# MCU.net
KiCad netlist of a schematic drawn in Altium Designer
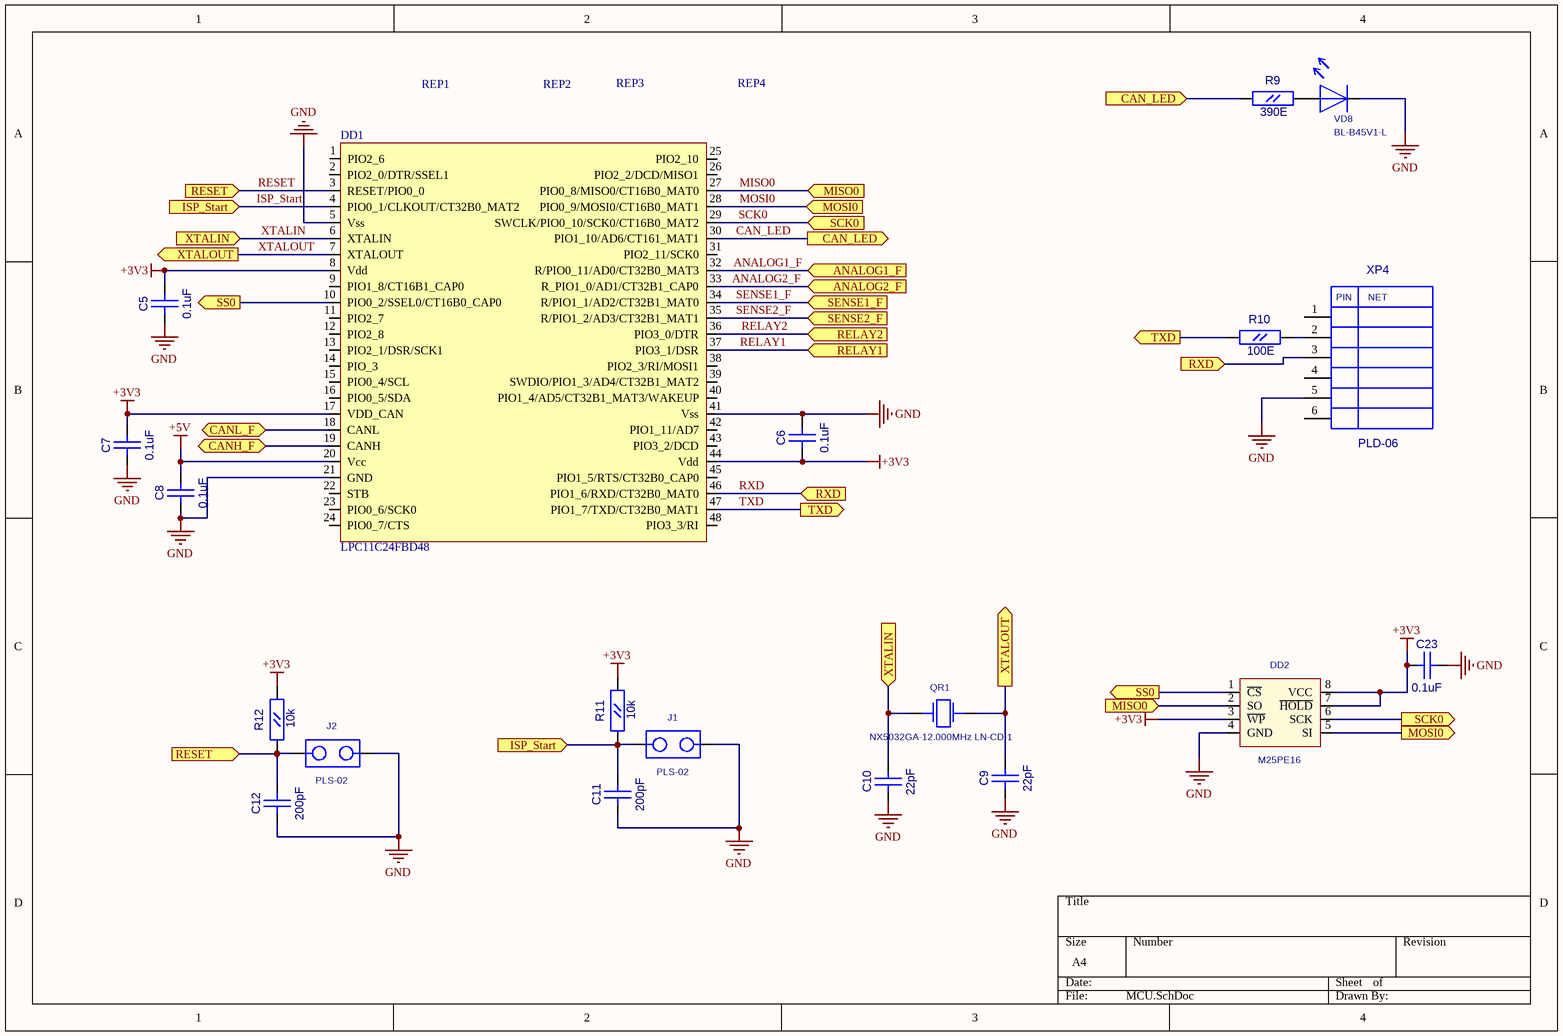
[diagram p0: MCU.SchDoc]

(export (version "E")
  (design (tool "Eeschema 10.0.6"))
  (components
    (comp (ref "C5")
      (value "0.1uF")
      (footprint "CC0603")
      (description "CC0603")
      (libsource (lib "gprs_modem_2") (part "CC0603"))
    )
    (comp (ref "C6")
      (value "0.1uF")
      (footprint "CC0603")
      (description "CC0603")
      (libsource (lib "gprs_modem_2") (part "CC0603"))
    )
    (comp (ref "C7")
      (value "0.1uF")
      (footprint "CC0603")
      (description "CC0603")
      (libsource (lib "gprs_modem_2") (part "CC0603"))
    )
    (comp (ref "C8")
      (value "0.1uF")
      (footprint "CC0603")
      (description "CC0603")
      (libsource (lib "gprs_modem_2") (part "CC0603"))
    )
    (comp (ref "C9")
      (value "22pF")
      (footprint "CC0603")
      (description "CC0603")
      (libsource (lib "gprs_modem_2") (part "CC0603"))
    )
    (comp (ref "C10")
      (value "22pF")
      (footprint "CC0603")
      (description "CC0603")
      (libsource (lib "gprs_modem_2") (part "CC0603"))
    )
    (comp (ref "C11")
      (value "200pF")
      (footprint "CC0603")
      (description "CC0603")
      (libsource (lib "gprs_modem_2") (part "CC0603"))
    )
    (comp (ref "C12")
      (value "200pF")
      (footprint "CC0603")
      (description "CC0603")
      (libsource (lib "gprs_modem_2") (part "CC0603"))
    )
    (comp (ref "C23")
      (value "0.1uF")
      (footprint "CC0603")
      (description "CC0603")
      (libsource (lib "gprs_modem_2") (part "CC0603"))
    )
    (comp (ref "DD1")
      (value "LPC11C24FBD48")
      (footprint "LQFP-48")
      (libsource (lib "gprs_modem_2") (part "LPC11C24FBD48"))
    )
    (comp (ref "DD2")
      (value "M25PE16")
      (footprint "EIAJ_SO8")
      (description "S25FL016A0LMFI01")
      (libsource (lib "gprs_modem_2") (part "S25FL016A0LMFI01"))
    )
    (comp (ref "J1") (value "PLS-02") (footprint "PLS-02") (libsource (lib "gprs_modem_2") (part "PLS-02")))
    (comp (ref "J2") (value "PLS-02") (footprint "PLS-02") (libsource (lib "gprs_modem_2") (part "PLS-02")))
    (comp (ref "QR1")
      (value "NX5032GA-12.000MHz LN-CD-1")
      (footprint "AC5032_2")
      (description "AC5032/2")
      (libsource (lib "gprs_modem_2") (part "AC5032_2"))
    )
    (comp (ref "R9")
      (value "390E")
      (footprint "RC0603")
      (description "RC0603")
      (libsource (lib "gprs_modem_2") (part "RC0603"))
    )
    (comp (ref "R10")
      (value "100E")
      (footprint "RC0603")
      (description "RC0603")
      (libsource (lib "gprs_modem_2") (part "RC0603"))
    )
    (comp (ref "R11")
      (value "10k")
      (footprint "RC0603")
      (description "RC0603")
      (libsource (lib "gprs_modem_2") (part "RC0603"))
    )
    (comp (ref "R12")
      (value "10k")
      (footprint "RC0603")
      (description "RC0603")
      (libsource (lib "gprs_modem_2") (part "RC0603"))
    )
    (comp (ref "REP1")
      (value "REPER_POINT_1.2")
      (footprint "REPER1.2")
      (description "REPER1.2")
      (libsource (lib "gprs_modem_2") (part "REPER1.2"))
    )
    (comp (ref "REP2")
      (value "REPER_POINT_1.2")
      (footprint "REPER1.2")
      (description "REPER1.2")
      (libsource (lib "gprs_modem_2") (part "REPER1.2"))
    )
    (comp (ref "REP3")
      (value "REPER_POINT_1.2")
      (footprint "REPER1.2")
      (description "REPER1.2")
      (libsource (lib "gprs_modem_2") (part "REPER1.2"))
    )
    (comp (ref "REP4")
      (value "REPER_POINT_1.2")
      (footprint "REPER1.2")
      (description "REPER1.2")
      (libsource (lib "gprs_modem_2") (part "REPER1.2"))
    )
    (comp (ref "VD8")
      (value "BL-B45V1-L")
      (footprint "LED3")
      (description "LED_3")
      (libsource (lib "gprs_modem_2") (part "LED_3"))
    )
    (comp (ref "XP4")
      (value "PLD-06")
      (footprint "PIN6")
      (description "PLD06")
      (libsource (lib "gprs_modem") (part "PLD-06"))
    )
  )
  (nets
    (net (code "1") (name "+3V3") (class "Default")
      (node (ref "C23") (pin "1") (pinfunction "A_1") (pintype "passive"))
      (node (ref "C5") (pin "2") (pinfunction "B_2") (pintype "passive"))
      (node (ref "C6") (pin "1") (pinfunction "A_1") (pintype "passive"))
      (node (ref "C7") (pin "2") (pinfunction "B_2") (pintype "passive"))
      (node (ref "DD1") (pin "17") (pinfunction "VDD_CAN_17") (pintype "passive"))
      (node (ref "DD1") (pin "44") (pinfunction "Vdd_44") (pintype "passive"))
      (node (ref "DD1") (pin "8") (pinfunction "Vdd_8") (pintype "passive"))
      (node (ref "DD2") (pin "3") (pinfunction "~{WP}_3") (pintype "passive"))
      (node (ref "DD2") (pin "7") (pinfunction "~{HOLD}_7") (pintype "passive"))
      (node (ref "DD2") (pin "8") (pinfunction "VCC_8") (pintype "passive"))
      (node (ref "R11") (pin "2") (pinfunction "B_2") (pintype "passive"))
      (node (ref "R12") (pin "2") (pinfunction "B_2") (pintype "passive"))
    )
    (net (code "2") (name "+5V") (class "Default")
      (node (ref "C8") (pin "2") (pinfunction "B_2") (pintype "passive"))
      (node (ref "DD1") (pin "20") (pinfunction "Vcc_20") (pintype "passive"))
    )
    (net (code "3") (name "/ANALOG1_F") (class "Default")
      (node (ref "DD1") (pin "32") (pinfunction "R/PIO0_11/AD0/CT32B0_MAT3_32") (pintype "passive"))
    )
    (net (code "4") (name "/ANALOG2_F") (class "Default")
      (node (ref "DD1") (pin "33") (pinfunction "R_PIO1_0/AD1/CT32B1_CAP0_33") (pintype "passive"))
    )
    (net (code "5") (name "/CANH_F") (class "Default")
      (node (ref "DD1") (pin "19") (pinfunction "CANH_19") (pintype "passive"))
    )
    (net (code "6") (name "/CANL_F") (class "Default")
      (node (ref "DD1") (pin "18") (pinfunction "CANL_18") (pintype "passive"))
    )
    (net (code "7") (name "/CAN_LED") (class "Default")
      (node (ref "DD1") (pin "30") (pinfunction "PIO1_10/AD6/CT161_MAT1_30") (pintype "passive"))
      (node (ref "R9") (pin "1") (pinfunction "A_1") (pintype "passive"))
    )
    (net (code "8") (name "/ISP_Start") (class "Default")
      (node (ref "C11") (pin "2") (pinfunction "B_2") (pintype "passive"))
      (node (ref "DD1") (pin "4") (pinfunction "PIO0_1/CLKOUT/CT32B0_MAT2_4") (pintype "passive"))
      (node (ref "J1") (pin "1") (pintype "passive"))
      (node (ref "R11") (pin "1") (pinfunction "A_1") (pintype "passive"))
    )
    (net (code "9") (name "/MISO0") (class "Default")
      (node (ref "DD1") (pin "27") (pinfunction "PIO0_8/MISO0/CT16B0_MAT0_27") (pintype "passive"))
      (node (ref "DD2") (pin "2") (pinfunction "SO_2") (pintype "passive"))
    )
    (net (code "10") (name "/MOSI0") (class "Default")
      (node (ref "DD1") (pin "28") (pinfunction "PIO0_9/MOSI0/CT16B0_MAT1_28") (pintype "passive"))
      (node (ref "DD2") (pin "5") (pinfunction "SI_5") (pintype "passive"))
    )
    (net (code "11") (name "/RELAY1") (class "Default")
      (node (ref "DD1") (pin "37") (pinfunction "PIO3_1/DSR_37") (pintype "passive"))
    )
    (net (code "12") (name "/RELAY2") (class "Default")
      (node (ref "DD1") (pin "36") (pinfunction "PIO3_0/DTR_36") (pintype "passive"))
    )
    (net (code "13") (name "/RESET") (class "Default")
      (node (ref "C12") (pin "2") (pinfunction "B_2") (pintype "passive"))
      (node (ref "DD1") (pin "3") (pinfunction "RESET/PIO0_0_3") (pintype "passive"))
      (node (ref "J2") (pin "1") (pintype "passive"))
      (node (ref "R12") (pin "1") (pinfunction "A_1") (pintype "passive"))
    )
    (net (code "14") (name "/RXD") (class "Default")
      (node (ref "DD1") (pin "46") (pinfunction "PIO1_6/RXD/CT32B0_MAT0_46") (pintype "passive"))
      (node (ref "XP4") (pin "3") (pinfunction "3_3") (pintype "passive"))
    )
    (net (code "15") (name "/SCK0") (class "Default")
      (node (ref "DD1") (pin "29") (pinfunction "SWCLK/PIO0_10/SCK0/CT16B0_MAT2_29") (pintype "passive"))
      (node (ref "DD2") (pin "6") (pinfunction "SCK_6") (pintype "passive"))
    )
    (net (code "16") (name "/SENSE1_F") (class "Default")
      (node (ref "DD1") (pin "34") (pinfunction "R/PIO1_1/AD2/CT32B1_MAT0_34") (pintype "passive"))
    )
    (net (code "17") (name "/SENSE2_F") (class "Default")
      (node (ref "DD1") (pin "35") (pinfunction "R/PIO1_2/AD3/CT32B1_MAT1_35") (pintype "passive"))
    )
    (net (code "18") (name "/SS0") (class "Default")
      (node (ref "DD1") (pin "10") (pinfunction "PIO0_2/SSEL0/CT16B0_CAP0_10") (pintype "passive"))
      (node (ref "DD2") (pin "1") (pinfunction "~{CS}_1") (pintype "passive"))
    )
    (net (code "19") (name "/TXD") (class "Default")
      (node (ref "DD1") (pin "47") (pinfunction "PIO1_7/TXD/CT32B0_MAT1_47") (pintype "passive"))
      (node (ref "R10") (pin "1") (pinfunction "A_1") (pintype "passive"))
    )
    (net (code "20") (name "/XTALIN") (class "Default")
      (node (ref "C10") (pin "2") (pinfunction "B_2") (pintype "passive"))
      (node (ref "DD1") (pin "6") (pinfunction "XTALIN_6") (pintype "passive"))
      (node (ref "QR1") (pin "1") (pintype "passive"))
    )
    (net (code "21") (name "/XTALOUT") (class "Default")
      (node (ref "C9") (pin "2") (pinfunction "B_2") (pintype "passive"))
      (node (ref "DD1") (pin "7") (pinfunction "XTALOUT_7") (pintype "passive"))
      (node (ref "QR1") (pin "2") (pintype "passive"))
    )
    (net (code "22") (name "GND") (class "Default")
      (node (ref "C10") (pin "1") (pinfunction "A_1") (pintype "passive"))
      (node (ref "C11") (pin "1") (pinfunction "A_1") (pintype "passive"))
      (node (ref "C12") (pin "1") (pinfunction "A_1") (pintype "passive"))
      (node (ref "C23") (pin "2") (pinfunction "B_2") (pintype "passive"))
      (node (ref "C5") (pin "1") (pinfunction "A_1") (pintype "passive"))
      (node (ref "C6") (pin "2") (pinfunction "B_2") (pintype "passive"))
      (node (ref "C7") (pin "1") (pinfunction "A_1") (pintype "passive"))
      (node (ref "C8") (pin "1") (pinfunction "A_1") (pintype "passive"))
      (node (ref "C9") (pin "1") (pinfunction "A_1") (pintype "passive"))
      (node (ref "DD1") (pin "21") (pinfunction "GND_21") (pintype "passive"))
      (node (ref "DD1") (pin "41") (pinfunction "Vss_41") (pintype "passive"))
      (node (ref "DD1") (pin "5") (pinfunction "Vss_5") (pintype "passive"))
      (node (ref "DD2") (pin "4") (pinfunction "GND_4") (pintype "passive"))
      (node (ref "J1") (pin "2") (pintype "passive"))
      (node (ref "J2") (pin "2") (pintype "passive"))
      (node (ref "VD8") (pin "1") (pintype "passive"))
      (node (ref "XP4") (pin "5") (pinfunction "5_5") (pintype "passive"))
    )
    (net (code "23") (name "Net-(R9-B)") (class "Default")
      (node (ref "R9") (pin "2") (pinfunction "B_2") (pintype "passive"))
      (node (ref "VD8") (pin "2") (pintype "passive"))
    )
    (net (code "24") (name "Net-(R10-B)") (class "Default")
      (node (ref "R10") (pin "2") (pinfunction "B_2") (pintype "passive"))
      (node (ref "XP4") (pin "2") (pinfunction "2_2") (pintype "passive"))
    )
    (net (code "25") (name "unconnected-(DD1-PIO0_4{slash}SCL-Pad15)") (class "Default")
      (node (ref "DD1") (pin "15") (pinfunction "PIO0_4/SCL_15") (pintype "passive"))
    )
    (net (code "26") (name "unconnected-(DD1-PIO0_5{slash}SDA-Pad16)") (class "Default")
      (node (ref "DD1") (pin "16") (pinfunction "PIO0_5/SDA_16") (pintype "passive"))
    )
    (net (code "27") (name "unconnected-(DD1-PIO0_6{slash}SCK0-Pad23)") (class "Default")
      (node (ref "DD1") (pin "23") (pinfunction "PIO0_6/SCK0_23") (pintype "passive"))
    )
    (net (code "28") (name "unconnected-(DD1-PIO0_7{slash}CTS-Pad24)") (class "Default")
      (node (ref "DD1") (pin "24") (pinfunction "PIO0_7/CTS_24") (pintype "passive"))
    )
    (net (code "29") (name "unconnected-(DD1-PIO1_4{slash}AD5{slash}CT32B1_MAT3{slash}WAKEUP-Pad40)") (class "Default")
      (node (ref "DD1") (pin "40") (pinfunction "PIO1_4/AD5/CT32B1_MAT3/WAKEUP_40") (pintype "passive"))
    )
    (net (code "30") (name "unconnected-(DD1-PIO1_5{slash}RTS{slash}CT32B0_CAP0-Pad45)") (class "Default")
      (node (ref "DD1") (pin "45") (pinfunction "PIO1_5/RTS/CT32B0_CAP0_45") (pintype "passive"))
    )
    (net (code "31") (name "unconnected-(DD1-PIO1_8{slash}CT16B1_CAP0-Pad9)") (class "Default")
      (node (ref "DD1") (pin "9") (pinfunction "PIO1_8/CT16B1_CAP0_9") (pintype "passive"))
    )
    (net (code "32") (name "unconnected-(DD1-PIO1_11{slash}AD7-Pad42)") (class "Default")
      (node (ref "DD1") (pin "42") (pinfunction "PIO1_11/AD7_42") (pintype "passive"))
    )
    (net (code "33") (name "unconnected-(DD1-PIO2_0{slash}DTR{slash}SSEL1-Pad2)") (class "Default")
      (node (ref "DD1") (pin "2") (pinfunction "PIO2_0/DTR/SSEL1_2") (pintype "passive"))
    )
    (net (code "34") (name "unconnected-(DD1-PIO2_1{slash}DSR{slash}SCK1-Pad13)") (class "Default")
      (node (ref "DD1") (pin "13") (pinfunction "PIO2_1/DSR/SCK1_13") (pintype "passive"))
    )
    (net (code "35") (name "unconnected-(DD1-PIO2_2{slash}DCD{slash}MISO1-Pad26)") (class "Default")
      (node (ref "DD1") (pin "26") (pinfunction "PIO2_2/DCD/MISO1_26") (pintype "passive"))
    )
    (net (code "36") (name "unconnected-(DD1-PIO2_3{slash}RI{slash}MOSI1-Pad38)") (class "Default")
      (node (ref "DD1") (pin "38") (pinfunction "PIO2_3/RI/MOSI1_38") (pintype "passive"))
    )
    (net (code "37") (name "unconnected-(DD1-PIO2_6-Pad1)") (class "Default")
      (node (ref "DD1") (pin "1") (pinfunction "PIO2_6_1") (pintype "passive"))
    )
    (net (code "38") (name "unconnected-(DD1-PIO2_7-Pad11)") (class "Default")
      (node (ref "DD1") (pin "11") (pinfunction "PIO2_7_11") (pintype "passive"))
    )
    (net (code "39") (name "unconnected-(DD1-PIO2_8-Pad12)") (class "Default")
      (node (ref "DD1") (pin "12") (pinfunction "PIO2_8_12") (pintype "passive"))
    )
    (net (code "40") (name "unconnected-(DD1-PIO2_10-Pad25)") (class "Default")
      (node (ref "DD1") (pin "25") (pinfunction "PIO2_10_25") (pintype "passive"))
    )
    (net (code "41") (name "unconnected-(DD1-PIO2_11{slash}SCK0-Pad31)") (class "Default")
      (node (ref "DD1") (pin "31") (pinfunction "PIO2_11/SCK0_31") (pintype "passive"))
    )
    (net (code "42") (name "unconnected-(DD1-PIO3_2{slash}DCD-Pad43)") (class "Default")
      (node (ref "DD1") (pin "43") (pinfunction "PIO3_2/DCD_43") (pintype "passive"))
    )
    (net (code "43") (name "unconnected-(DD1-PIO3_3{slash}RI-Pad48)") (class "Default")
      (node (ref "DD1") (pin "48") (pinfunction "PIO3_3/RI_48") (pintype "passive"))
    )
    (net (code "44") (name "unconnected-(DD1-PIO_3-Pad14)") (class "Default")
      (node (ref "DD1") (pin "14") (pinfunction "PIO_3_14") (pintype "passive"))
    )
    (net (code "45") (name "unconnected-(DD1-STB-Pad22)") (class "Default")
      (node (ref "DD1") (pin "22") (pinfunction "STB_22") (pintype "passive"))
    )
    (net (code "46") (name "unconnected-(DD1-SWDIO{slash}PIO1_3{slash}AD4{slash}CT32B1_MAT2-Pad39)") (class "Default")
      (node (ref "DD1") (pin "39") (pinfunction "SWDIO/PIO1_3/AD4/CT32B1_MAT2_39") (pintype "passive"))
    )
    (net (code "47") (name "unconnected-(REP1-Pad1)") (class "Default")
      (node (ref "REP1") (pin "1") (pintype "passive"))
    )
    (net (code "48") (name "unconnected-(REP2-Pad1)") (class "Default")
      (node (ref "REP2") (pin "1") (pintype "passive"))
    )
    (net (code "49") (name "unconnected-(REP3-Pad1)") (class "Default")
      (node (ref "REP3") (pin "1") (pintype "passive"))
    )
    (net (code "50") (name "unconnected-(REP4-Pad1)") (class "Default")
      (node (ref "REP4") (pin "1") (pintype "passive"))
    )
    (net (code "51") (name "unconnected-(XP4-Pad1)") (class "Default")
      (node (ref "XP4") (pin "1") (pinfunction "1_1") (pintype "passive"))
    )
    (net (code "52") (name "unconnected-(XP4-Pad4)") (class "Default")
      (node (ref "XP4") (pin "4") (pinfunction "4_4") (pintype "passive"))
    )
    (net (code "53") (name "unconnected-(XP4-Pad6)") (class "Default")
      (node (ref "XP4") (pin "6") (pinfunction "6_6") (pintype "passive"))
    )
  )
)
